# AFE.net
KiCad netlist of a schematic drawn in EAGLE
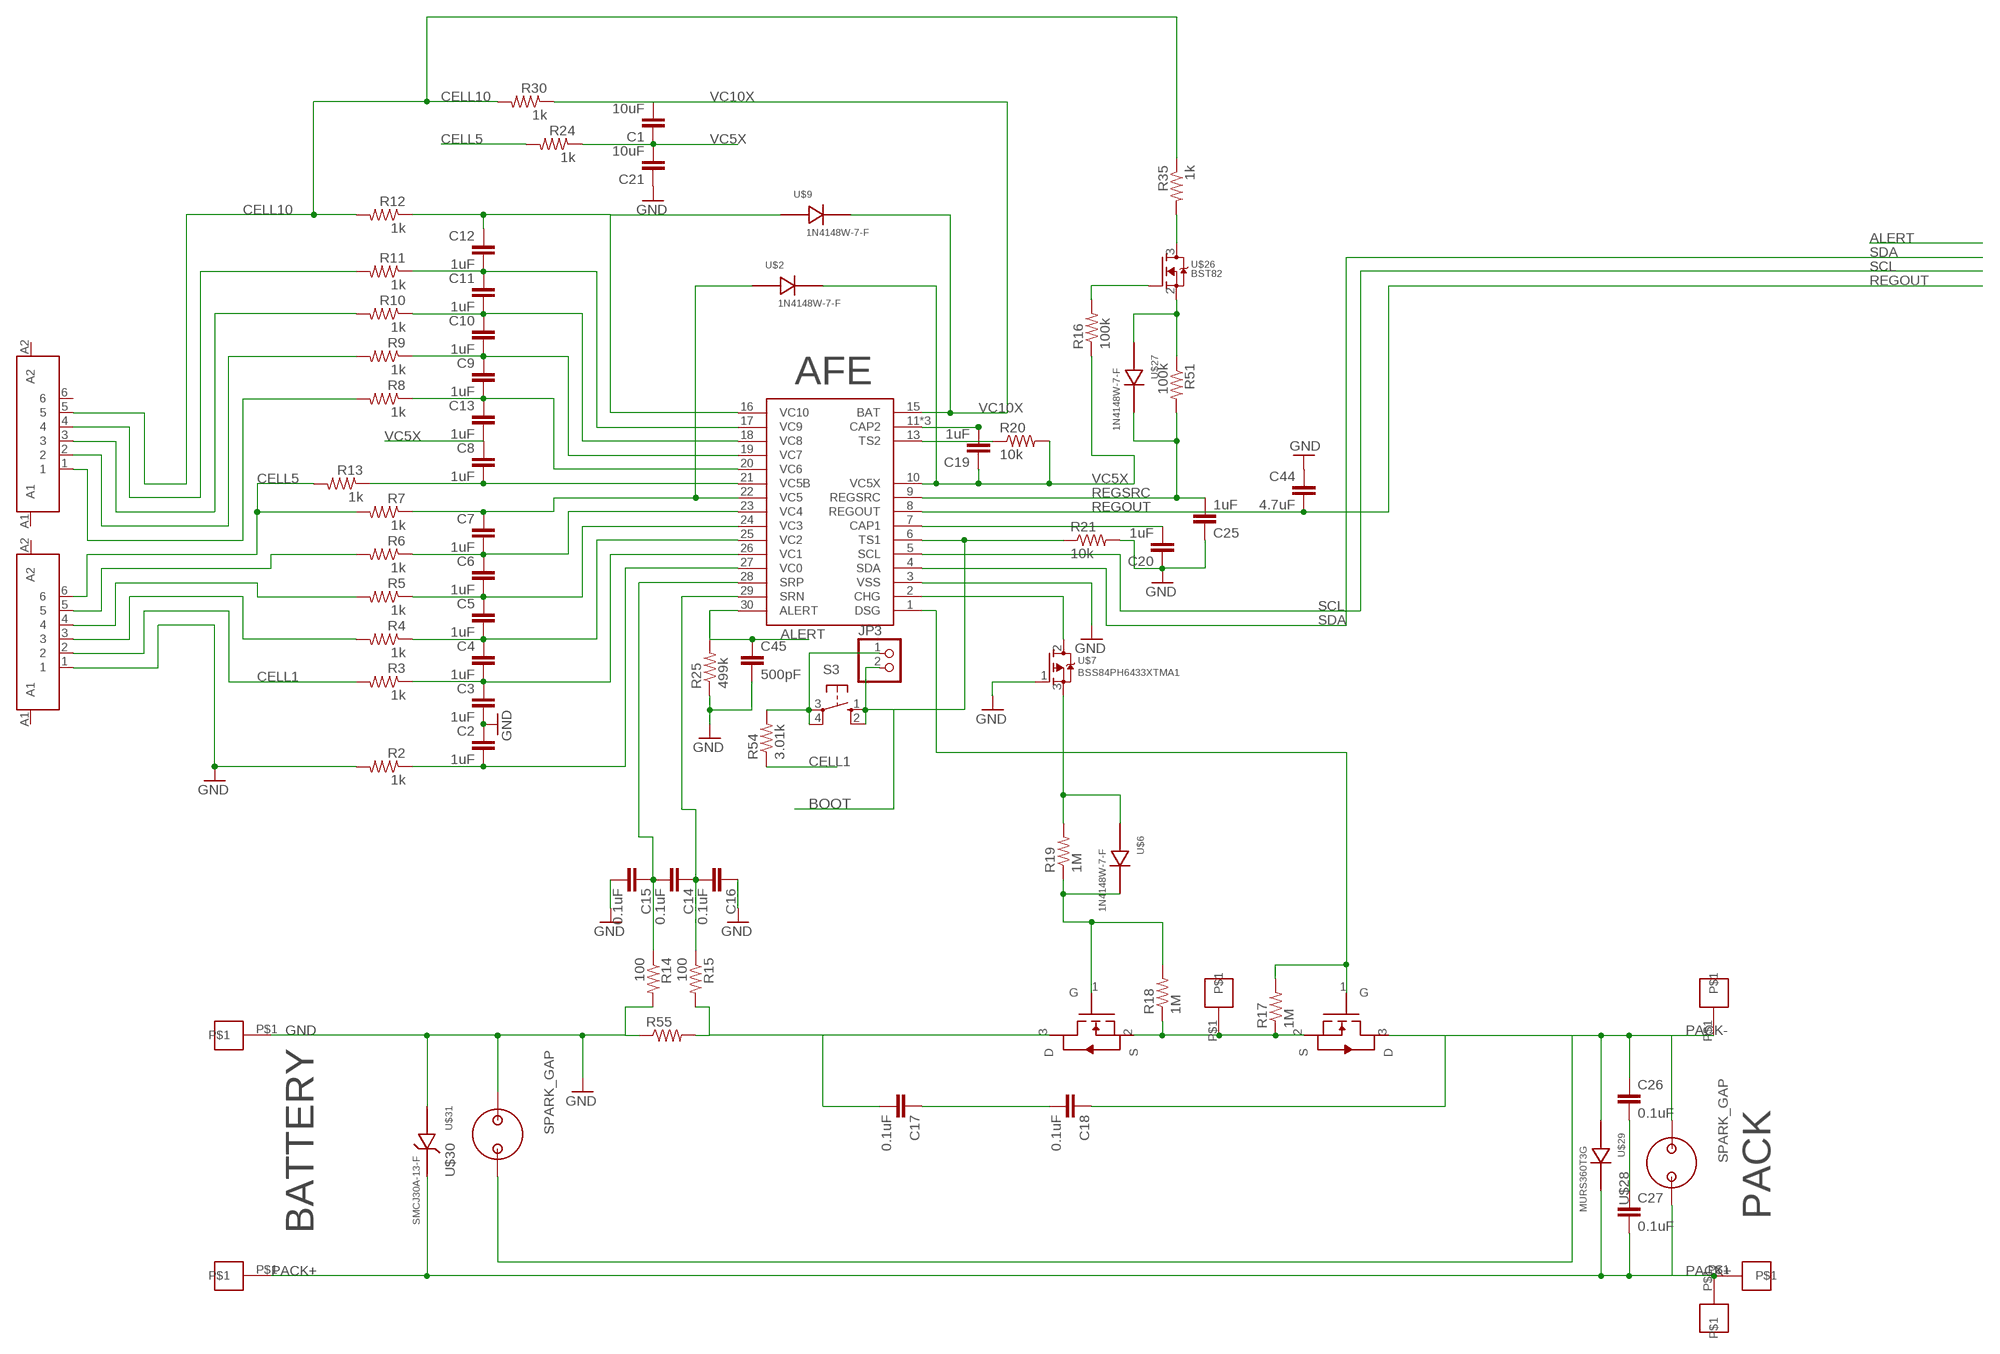
[diagram p0: schematic, sheet 1]
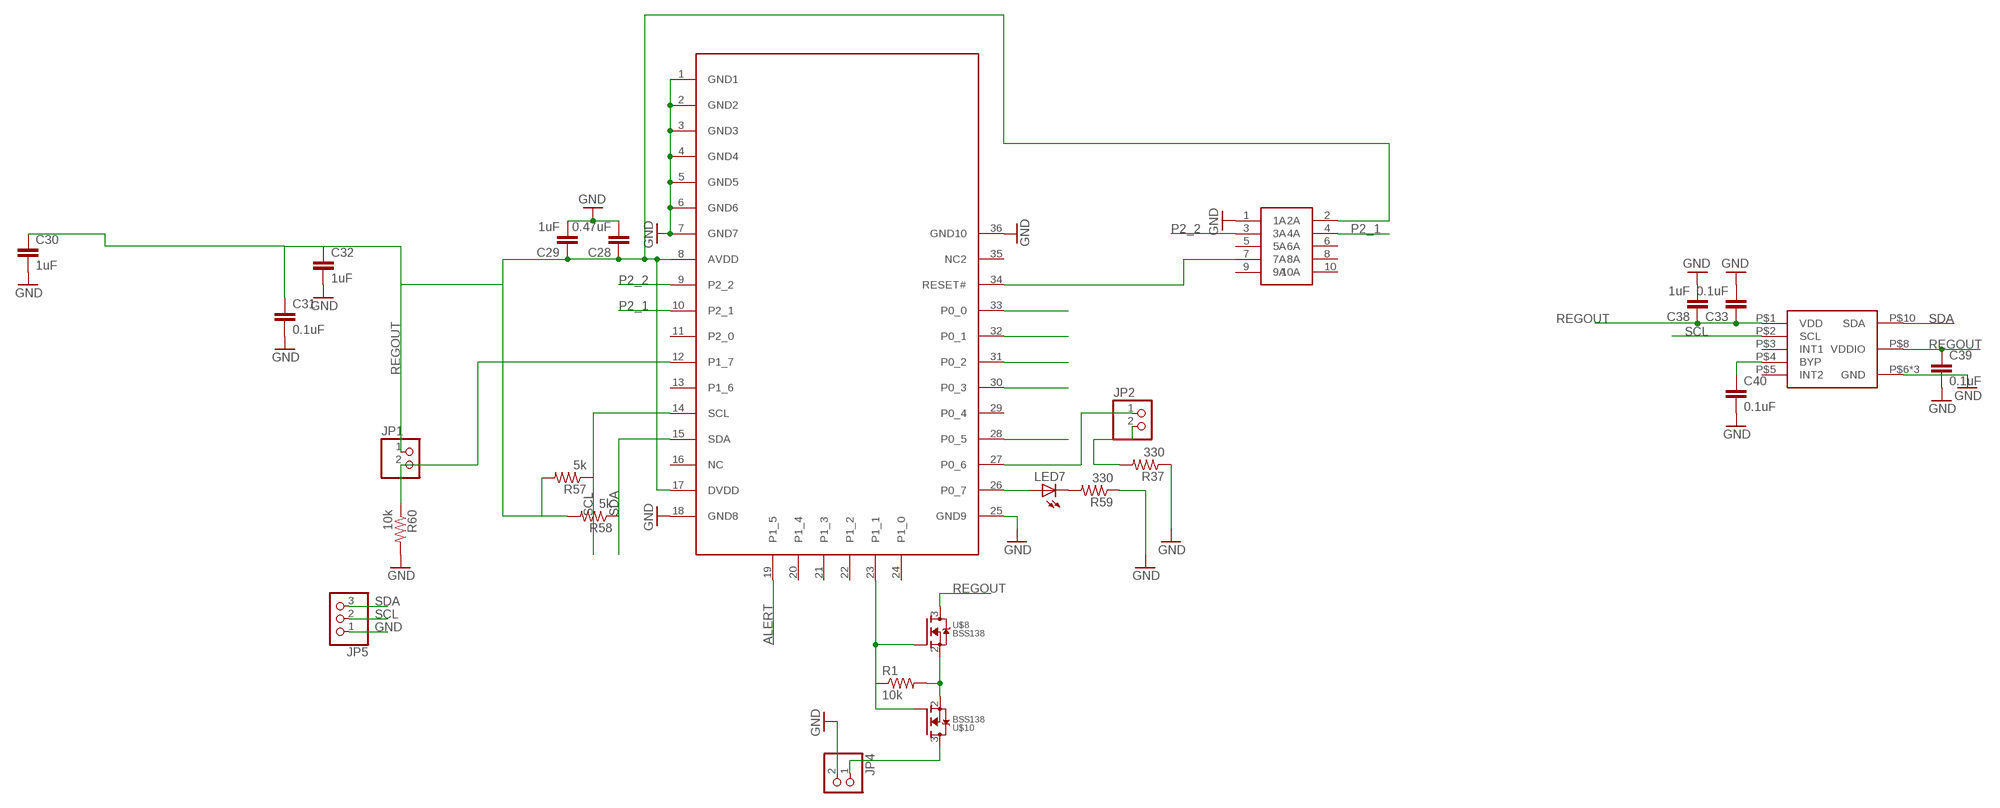
[diagram p1: schematic, sheet 2]

(export (version "E")
  (design (tool "Eeschema 10.0.6"))
  (components
    (comp (ref "C28")
      (value "0.47uF")
      (footprint "eagle-import:C0402")
      (libsource (lib "eagle-import") (part "C-EUC0402"))
    )
    (comp (ref "C29")
      (value "1uF")
      (footprint "eagle-import:C0402")
      (libsource (lib "eagle-import") (part "C-EUC0402"))
    )
    (comp (ref "C30")
      (value "1uF")
      (footprint "eagle-import:C0402")
      (libsource (lib "eagle-import") (part "C-EUC0402"))
    )
    (comp (ref "C31")
      (value "0.1uF")
      (footprint "eagle-import:C0402")
      (libsource (lib "eagle-import") (part "C-EUC0402"))
    )
    (comp (ref "C32")
      (value "1uF")
      (footprint "eagle-import:C0402")
      (libsource (lib "eagle-import") (part "C-EUC0402"))
    )
    (comp (ref "C33")
      (value "0.1uF")
      (footprint "eagle-import:C0402")
      (libsource (lib "eagle-import") (part "C-EUC0402"))
    )
    (comp (ref "C38")
      (value "1uF")
      (footprint "eagle-import:C0402")
      (libsource (lib "eagle-import") (part "C-EUC0402"))
    )
    (comp (ref "C39")
      (value "0.1uF")
      (footprint "eagle-import:C0402")
      (libsource (lib "eagle-import") (part "C-EUC0402"))
    )
    (comp (ref "C40")
      (value "0.1uF")
      (footprint "eagle-import:C0402")
      (libsource (lib "eagle-import") (part "C-EUC0402"))
    )
    (comp (ref "JP1")
      (value "PINHD-1X2")
      (footprint "eagle-import:1X02")
      (libsource (lib "eagle-import") (part "PINHD-1X2"))
    )
    (comp (ref "JP2")
      (value "PINHD-1X2")
      (footprint "eagle-import:1X02")
      (libsource (lib "eagle-import") (part "PINHD-1X2"))
    )
    (comp (ref "JP4")
      (value "PINHD-1X2")
      (footprint "eagle-import:1X02")
      (libsource (lib "eagle-import") (part "PINHD-1X2"))
    )
    (comp (ref "JP5")
      (value "PINHD-1X3")
      (footprint "eagle-import:1X03")
      (libsource (lib "eagle-import") (part "PINHD-1X3"))
    )
    (comp (ref "LED7")
      (value "LEDCHIP-LED0603")
      (footprint "eagle-import:CHIP-LED0603")
      (libsource (lib "eagle-import") (part "LEDCHIP-LED0603"))
    )
    (comp (ref "R1")
      (value "10k")
      (footprint "eagle-import:R0402")
      (libsource (lib "eagle-import") (part "R-US_R0402"))
    )
    (comp (ref "R37")
      (value "330")
      (footprint "eagle-import:R0402")
      (libsource (lib "eagle-import") (part "R-US_R0402"))
    )
    (comp (ref "R57")
      (value "5k")
      (footprint "eagle-import:R0402")
      (libsource (lib "eagle-import") (part "R-US_R0402"))
    )
    (comp (ref "R58")
      (value "5k")
      (footprint "eagle-import:R0402")
      (libsource (lib "eagle-import") (part "R-US_R0402"))
    )
    (comp (ref "R59")
      (value "330")
      (footprint "eagle-import:R0402")
      (libsource (lib "eagle-import") (part "R-US_R0402"))
    )
    (comp (ref "R60")
      (value "10k")
      (footprint "eagle-import:R0402")
      (libsource (lib "eagle-import") (part "R-US_R0402"))
    )
    (comp (ref "U$8")
      (value "BSS138")
      (footprint "eagle-import:SOT23-3")
      (libsource (lib "eagle-import") (part "BSS138"))
    )
    (comp (ref "U$10")
      (value "BSS138")
      (footprint "eagle-import:SOT23-3")
      (libsource (lib "eagle-import") (part "BSS138"))
    )
    (comp (ref "U$20")
      (value "BLE113")
      (footprint "eagle-import:BLUEGIGA")
      (libsource (lib "eagle-import") (part "BLE113"))
    )
    (comp (ref "U$22")
      (value "RIBBON_10POS_MALE")
      (footprint "eagle-import:RIBBON_10POS_MALE")
      (libsource (lib "eagle-import") (part "RIBBON_10POS_MALE"))
    )
    (comp (ref "U$32")
      (value "MMA8653FC")
      (footprint "eagle-import:10-DFN2X2")
      (libsource (lib "eagle-import") (part "MMA8653FC"))
    )
    (comp (ref "C1")
      (value "10uF")
      (footprint "eagle-import:C1210")
      (libsource (lib "eagle-import") (part "C-EUC1210"))
    )
    (comp (ref "C2")
      (value "1uF")
      (footprint "eagle-import:C0805")
      (libsource (lib "eagle-import") (part "C-EUC0805"))
    )
    (comp (ref "C3")
      (value "1uF")
      (footprint "eagle-import:C0805")
      (libsource (lib "eagle-import") (part "C-EUC0805"))
    )
    (comp (ref "C4")
      (value "1uF")
      (footprint "eagle-import:C0805")
      (libsource (lib "eagle-import") (part "C-EUC0805"))
    )
    (comp (ref "C5")
      (value "1uF")
      (footprint "eagle-import:C0805")
      (libsource (lib "eagle-import") (part "C-EUC0805"))
    )
    (comp (ref "C6")
      (value "1uF")
      (footprint "eagle-import:C0805")
      (libsource (lib "eagle-import") (part "C-EUC0805"))
    )
    (comp (ref "C7")
      (value "1uF")
      (footprint "eagle-import:C0805")
      (libsource (lib "eagle-import") (part "C-EUC0805"))
    )
    (comp (ref "C8")
      (value "1uF")
      (footprint "eagle-import:C0805")
      (libsource (lib "eagle-import") (part "C-EUC0805"))
    )
    (comp (ref "C9")
      (value "1uF")
      (footprint "eagle-import:C0805")
      (libsource (lib "eagle-import") (part "C-EUC0805"))
    )
    (comp (ref "C10")
      (value "1uF")
      (footprint "eagle-import:C0805")
      (libsource (lib "eagle-import") (part "C-EUC0805"))
    )
    (comp (ref "C11")
      (value "1uF")
      (footprint "eagle-import:C0805")
      (libsource (lib "eagle-import") (part "C-EUC0805"))
    )
    (comp (ref "C12")
      (value "1uF")
      (footprint "eagle-import:C0805")
      (libsource (lib "eagle-import") (part "C-EUC0805"))
    )
    (comp (ref "C13")
      (value "1uF")
      (footprint "eagle-import:C0805")
      (libsource (lib "eagle-import") (part "C-EUC0805"))
    )
    (comp (ref "C14")
      (value "0.1uF")
      (footprint "eagle-import:C0805")
      (libsource (lib "eagle-import") (part "C-EUC0805"))
    )
    (comp (ref "C15")
      (value "0.1uF")
      (footprint "eagle-import:C0805")
      (libsource (lib "eagle-import") (part "C-EUC0805"))
    )
    (comp (ref "C16")
      (value "0.1uF")
      (footprint "eagle-import:C0805")
      (libsource (lib "eagle-import") (part "C-EUC0805"))
    )
    (comp (ref "C17")
      (value "0.1uF")
      (footprint "eagle-import:C0805")
      (libsource (lib "eagle-import") (part "C-EUC0805"))
    )
    (comp (ref "C18")
      (value "0.1uF")
      (footprint "eagle-import:C0805")
      (libsource (lib "eagle-import") (part "C-EUC0805"))
    )
    (comp (ref "C19")
      (value "1uF")
      (footprint "eagle-import:C0805")
      (libsource (lib "eagle-import") (part "C-EUC0805"))
    )
    (comp (ref "C20")
      (value "1uF")
      (footprint "eagle-import:C0805")
      (libsource (lib "eagle-import") (part "C-EUC0805"))
    )
    (comp (ref "C21")
      (value "10uF")
      (footprint "eagle-import:C1210")
      (libsource (lib "eagle-import") (part "C-EUC1210"))
    )
    (comp (ref "C25")
      (value "1uF")
      (footprint "eagle-import:C0805")
      (libsource (lib "eagle-import") (part "C-EUC0805"))
    )
    (comp (ref "C26")
      (value "0.1uF")
      (footprint "eagle-import:C0805")
      (libsource (lib "eagle-import") (part "C-EUC0805"))
    )
    (comp (ref "C27")
      (value "0.1uF")
      (footprint "eagle-import:C0805")
      (libsource (lib "eagle-import") (part "C-EUC0805"))
    )
    (comp (ref "C44")
      (value "4.7uF")
      (footprint "eagle-import:C0805")
      (libsource (lib "eagle-import") (part "C-EUC0805"))
    )
    (comp (ref "C45")
      (value "500pF")
      (footprint "eagle-import:C0603")
      (libsource (lib "eagle-import") (part "C-EUC0603"))
    )
    (comp (ref "JP3")
      (value "PINHD-1X2")
      (footprint "eagle-import:1X02")
      (libsource (lib "eagle-import") (part "PINHD-1X2"))
    )
    (comp (ref "R2")
      (value "1k")
      (footprint "eagle-import:R1206")
      (libsource (lib "eagle-import") (part "R-US_R1206"))
    )
    (comp (ref "R3")
      (value "1k")
      (footprint "eagle-import:R1206")
      (libsource (lib "eagle-import") (part "R-US_R1206"))
    )
    (comp (ref "R4")
      (value "1k")
      (footprint "eagle-import:R1206")
      (libsource (lib "eagle-import") (part "R-US_R1206"))
    )
    (comp (ref "R5")
      (value "1k")
      (footprint "eagle-import:R1206")
      (libsource (lib "eagle-import") (part "R-US_R1206"))
    )
    (comp (ref "R6")
      (value "1k")
      (footprint "eagle-import:R1206")
      (libsource (lib "eagle-import") (part "R-US_R1206"))
    )
    (comp (ref "R7")
      (value "1k")
      (footprint "eagle-import:R1206")
      (libsource (lib "eagle-import") (part "R-US_R1206"))
    )
    (comp (ref "R8")
      (value "1k")
      (footprint "eagle-import:R1206")
      (libsource (lib "eagle-import") (part "R-US_R1206"))
    )
    (comp (ref "R9")
      (value "1k")
      (footprint "eagle-import:R1206")
      (libsource (lib "eagle-import") (part "R-US_R1206"))
    )
    (comp (ref "R10")
      (value "1k")
      (footprint "eagle-import:R1206")
      (libsource (lib "eagle-import") (part "R-US_R1206"))
    )
    (comp (ref "R11")
      (value "1k")
      (footprint "eagle-import:R1206")
      (libsource (lib "eagle-import") (part "R-US_R1206"))
    )
    (comp (ref "R12")
      (value "1k")
      (footprint "eagle-import:R1206")
      (libsource (lib "eagle-import") (part "R-US_R1206"))
    )
    (comp (ref "R13")
      (value "1k")
      (footprint "eagle-import:R1206")
      (libsource (lib "eagle-import") (part "R-US_R1206"))
    )
    (comp (ref "R14")
      (value "100")
      (footprint "eagle-import:R0805")
      (libsource (lib "eagle-import") (part "R-US_R0805"))
    )
    (comp (ref "R15")
      (value "100")
      (footprint "eagle-import:R0805")
      (libsource (lib "eagle-import") (part "R-US_R0805"))
    )
    (comp (ref "R16")
      (value "100k")
      (footprint "eagle-import:R0805")
      (libsource (lib "eagle-import") (part "R-US_R0805"))
    )
    (comp (ref "R17")
      (value "1M")
      (footprint "eagle-import:R1206")
      (libsource (lib "eagle-import") (part "R-US_R1206"))
    )
    (comp (ref "R18")
      (value "1M")
      (footprint "eagle-import:R1206")
      (libsource (lib "eagle-import") (part "R-US_R1206"))
    )
    (comp (ref "R19")
      (value "1M")
      (footprint "eagle-import:R1206")
      (libsource (lib "eagle-import") (part "R-US_R1206"))
    )
    (comp (ref "R20")
      (value "10k")
      (footprint "eagle-import:R0805")
      (libsource (lib "eagle-import") (part "R-US_R0805"))
    )
    (comp (ref "R21")
      (value "10k")
      (footprint "eagle-import:R0805")
      (libsource (lib "eagle-import") (part "R-US_R0805"))
    )
    (comp (ref "R24")
      (value "1k")
      (footprint "eagle-import:R1206")
      (libsource (lib "eagle-import") (part "R-US_R1206"))
    )
    (comp (ref "R25")
      (value "499k")
      (footprint "eagle-import:R0603")
      (libsource (lib "eagle-import") (part "R-US_R0603"))
    )
    (comp (ref "R30")
      (value "1k")
      (footprint "eagle-import:R1206")
      (libsource (lib "eagle-import") (part "R-US_R1206"))
    )
    (comp (ref "R35")
      (value "1k")
      (footprint "eagle-import:R1206")
      (libsource (lib "eagle-import") (part "R-US_R1206"))
    )
    (comp (ref "R51")
      (value "100k")
      (footprint "eagle-import:R0805")
      (libsource (lib "eagle-import") (part "R-US_R0805"))
    )
    (comp (ref "R54")
      (value "3.01k")
      (footprint "eagle-import:R1206")
      (libsource (lib "eagle-import") (part "R-US_R1206"))
    )
    (comp (ref "R55")
      (value "R-US_R2512")
      (footprint "eagle-import:R2512")
      (libsource (lib "eagle-import") (part "R-US_R2512"))
    )
    (comp (ref "S3")
      (value "10-XX")
      (footprint "eagle-import:B3F-10XX")
      (fields (field (name "MPN") "B3F-1000"))
      (libsource (lib "eagle-import") (part "10-XX"))
    )
    (comp (ref "U$1")
      (value "BQ76930")
      (footprint "eagle-import:SOIC-30")
      (libsource (lib "eagle-import") (part "BQ76930"))
    )
    (comp (ref "U$2")
      (value "1N4148W-7-F")
      (footprint "eagle-import:SOD-123")
      (libsource (lib "eagle-import") (part "1N4148W-7-F"))
    )
    (comp (ref "U$3")
      (value "PAD")
      (footprint "eagle-import:PAD")
      (libsource (lib "eagle-import") (part "PAD"))
    )
    (comp (ref "U$4")
      (value "AOB290L")
      (footprint "eagle-import:TO-263")
      (libsource (lib "eagle-import") (part "AOB290L"))
    )
    (comp (ref "U$5")
      (value "AOB290L")
      (footprint "eagle-import:TO-263")
      (libsource (lib "eagle-import") (part "AOB290L"))
    )
    (comp (ref "U$6")
      (value "1N4148W-7-F")
      (footprint "eagle-import:SOD-123")
      (libsource (lib "eagle-import") (part "1N4148W-7-F"))
    )
    (comp (ref "U$7")
      (value "BSS84PH6433XTMA1")
      (footprint "eagle-import:SOT23-3")
      (libsource (lib "eagle-import") (part "BSS84PH6433XTMA1"))
    )
    (comp (ref "U$9")
      (value "1N4148W-7-F")
      (footprint "eagle-import:SOD-123")
      (libsource (lib "eagle-import") (part "1N4148W-7-F"))
    )
    (comp (ref "U$24")
      (value "JST_6PIN")
      (footprint "eagle-import:JST_6PIN")
      (libsource (lib "eagle-import") (part "JST_6PIN"))
    )
    (comp (ref "U$26")
      (value "BST82")
      (footprint "eagle-import:SOT23-3")
      (libsource (lib "eagle-import") (part "BST82"))
    )
    (comp (ref "U$27")
      (value "1N4148W-7-F")
      (footprint "eagle-import:SOD-123")
      (libsource (lib "eagle-import") (part "1N4148W-7-F"))
    )
    (comp (ref "U$28")
      (value "SPARK_GAP")
      (footprint "eagle-import:SPARK_GAP")
      (libsource (lib "eagle-import") (part "SPARK_GAP"))
    )
    (comp (ref "U$29")
      (value "MURS360T3G")
      (footprint "eagle-import:SMC(DO-214AB)")
      (libsource (lib "eagle-import") (part "MURS360T3G"))
    )
    (comp (ref "U$30")
      (value "SPARK_GAP")
      (footprint "eagle-import:SPARK_GAP")
      (libsource (lib "eagle-import") (part "SPARK_GAP"))
    )
    (comp (ref "U$31")
      (value "SMCJ30A-13-F")
      (footprint "eagle-import:SMB(DO-214AA)")
      (libsource (lib "eagle-import") (part "SMCJ30A-13-F"))
    )
    (comp (ref "U$33")
      (value "JST_6PIN")
      (footprint "eagle-import:JST_6PIN")
      (libsource (lib "eagle-import") (part "JST_6PIN"))
    )
    (comp (ref "U$35")
      (value "PAD")
      (footprint "eagle-import:PAD")
      (libsource (lib "eagle-import") (part "PAD"))
    )
    (comp (ref "U$36")
      (value "PAD")
      (footprint "eagle-import:PAD")
      (libsource (lib "eagle-import") (part "PAD"))
    )
    (comp (ref "U$37")
      (value "PAD")
      (footprint "eagle-import:PAD")
      (libsource (lib "eagle-import") (part "PAD"))
    )
    (comp (ref "U$38")
      (value "PAD")
      (footprint "eagle-import:PAD")
      (libsource (lib "eagle-import") (part "PAD"))
    )
    (comp (ref "U$39")
      (value "PAD")
      (footprint "eagle-import:PAD")
      (libsource (lib "eagle-import") (part "PAD"))
    )
  )
  (nets
    (net (code "1") (name "ALERT") (class "Default")
      (node (ref "C45") (pin "1") (pinfunction "1_1") (pintype "passive"))
      (node (ref "R25") (pin "2") (pinfunction "2_2") (pintype "passive"))
      (node (ref "U$1") (pin "30") (pinfunction "ALERT_30") (pintype "bidirectional"))
      (node (ref "U$20") (pin "19") (pinfunction "P1_5_19") (pintype "bidirectional"))
    )
    (net (code "2") (name "BOOT") (class "Default")
      (node (ref "JP3") (pin "2") (pinfunction "2_2") (pintype "passive"))
      (node (ref "R21") (pin "1") (pinfunction "1_1") (pintype "passive"))
      (node (ref "S3") (pin "1") (pinfunction "S_1") (pintype "passive"))
      (node (ref "S3") (pin "2") (pinfunction "S1_2") (pintype "passive"))
      (node (ref "U$1") (pin "6") (pinfunction "TS1_6") (pintype "bidirectional"))
    )
    (net (code "3") (name "CELL1") (class "Default")
      (node (ref "R3") (pin "2") (pinfunction "2_2") (pintype "passive"))
      (node (ref "R54") (pin "1") (pinfunction "1_1") (pintype "passive"))
      (node (ref "U$33") (pin "2") (pinfunction "2_2") (pintype "bidirectional"))
    )
    (net (code "4") (name "CELL5") (class "Default")
      (node (ref "R13") (pin "2") (pinfunction "2_2") (pintype "passive"))
      (node (ref "R24") (pin "2") (pinfunction "2_2") (pintype "passive"))
      (node (ref "R7") (pin "2") (pinfunction "2_2") (pintype "passive"))
      (node (ref "U$33") (pin "6") (pinfunction "6_6") (pintype "bidirectional"))
    )
    (net (code "5") (name "CELL10") (class "Default")
      (node (ref "R12") (pin "2") (pinfunction "2_2") (pintype "passive"))
      (node (ref "R30") (pin "2") (pinfunction "2_2") (pintype "passive"))
      (node (ref "R35") (pin "1") (pinfunction "1_1") (pintype "passive"))
      (node (ref "U$24") (pin "5") (pinfunction "5_5") (pintype "bidirectional"))
    )
    (net (code "6") (name "GND") (class "Default")
      (node (ref "C15") (pin "2") (pinfunction "2_2") (pintype "passive"))
      (node (ref "C16") (pin "1") (pinfunction "1_1") (pintype "passive"))
      (node (ref "C2") (pin "1") (pinfunction "1_1") (pintype "passive"))
      (node (ref "C20") (pin "1") (pinfunction "1_1") (pintype "passive"))
      (node (ref "C21") (pin "1") (pinfunction "1_1") (pintype "passive"))
      (node (ref "C25") (pin "1") (pinfunction "1_1") (pintype "passive"))
      (node (ref "C28") (pin "2") (pinfunction "2_2") (pintype "passive"))
      (node (ref "C29") (pin "2") (pinfunction "2_2") (pintype "passive"))
      (node (ref "C3") (pin "2") (pinfunction "2_2") (pintype "passive"))
      (node (ref "C30") (pin "2") (pinfunction "2_2") (pintype "passive"))
      (node (ref "C31") (pin "2") (pinfunction "2_2") (pintype "passive"))
      (node (ref "C32") (pin "2") (pinfunction "2_2") (pintype "passive"))
      (node (ref "C33") (pin "2") (pinfunction "2_2") (pintype "passive"))
      (node (ref "C38") (pin "2") (pinfunction "2_2") (pintype "passive"))
      (node (ref "C39") (pin "2") (pinfunction "2_2") (pintype "passive"))
      (node (ref "C40") (pin "2") (pinfunction "2_2") (pintype "passive"))
      (node (ref "C44") (pin "1") (pinfunction "1_1") (pintype "passive"))
      (node (ref "C45") (pin "2") (pinfunction "2_2") (pintype "passive"))
      (node (ref "JP4") (pin "2") (pinfunction "2_2") (pintype "passive"))
      (node (ref "JP5") (pin "1") (pinfunction "1_1") (pintype "passive"))
      (node (ref "R14") (pin "2") (pinfunction "2_2") (pintype "passive"))
      (node (ref "R2") (pin "2") (pinfunction "2_2") (pintype "passive"))
      (node (ref "R21") (pin "2") (pinfunction "2_2") (pintype "passive"))
      (node (ref "R25") (pin "1") (pinfunction "1_1") (pintype "passive"))
      (node (ref "R37") (pin "1") (pinfunction "1_1") (pintype "passive"))
      (node (ref "R55") (pin "1") (pinfunction "1_1") (pintype "passive"))
      (node (ref "R59") (pin "1") (pinfunction "1_1") (pintype "passive"))
      (node (ref "R60") (pin "2") (pinfunction "2_2") (pintype "passive"))
      (node (ref "U$1") (pin "3") (pinfunction "VSS_3") (pintype "bidirectional"))
      (node (ref "U$20") (pin "1") (pinfunction "GND1_1") (pintype "bidirectional"))
      (node (ref "U$20") (pin "18") (pinfunction "GND8_18") (pintype "bidirectional"))
      (node (ref "U$20") (pin "2") (pinfunction "GND2_2") (pintype "bidirectional"))
      (node (ref "U$20") (pin "25") (pinfunction "GND9_25") (pintype "bidirectional"))
      (node (ref "U$20") (pin "3") (pinfunction "GND3_3") (pintype "bidirectional"))
      (node (ref "U$20") (pin "36") (pinfunction "GND10_36") (pintype "bidirectional"))
      (node (ref "U$20") (pin "4") (pinfunction "GND4_4") (pintype "bidirectional"))
      (node (ref "U$20") (pin "5") (pinfunction "GND5_5") (pintype "bidirectional"))
      (node (ref "U$20") (pin "6") (pinfunction "GND6_6") (pintype "bidirectional"))
      (node (ref "U$20") (pin "7") (pinfunction "GND7_7") (pintype "bidirectional"))
      (node (ref "U$22") (pin "1") (pinfunction "1A_1") (pintype "bidirectional"))
      (node (ref "U$3") (pin "P$1") (pinfunction "P$1_P$1") (pintype "bidirectional"))
      (node (ref "U$30") (pin "P$2") (pinfunction "P$2_P$2") (pintype "bidirectional"))
      (node (ref "U$31") (pin "P$1") (pinfunction "1_P$1") (pintype "bidirectional"))
      (node (ref "U$32") (pin "P$6") (pinfunction "GND_P$6") (pintype "bidirectional"))
      (node (ref "U$32") (pin "P$7") (pinfunction "GND_P$7") (pintype "bidirectional"))
      (node (ref "U$32") (pin "P$9") (pinfunction "GND_P$9") (pintype "bidirectional"))
      (node (ref "U$33") (pin "1") (pinfunction "1_1") (pintype "bidirectional"))
      (node (ref "U$7") (pin "1") (pinfunction "G_1") (pintype "bidirectional"))
    )
    (net (code "7") (name "Net-(C17-Pad1)") (class "Default")
      (node (ref "C17") (pin "1") (pinfunction "1_1") (pintype "passive"))
      (node (ref "C18") (pin "2") (pinfunction "2_2") (pintype "passive"))
    )
    (net (code "8") (name "Net-(C19-Pad2)") (class "Default")
      (node (ref "C19") (pin "2") (pinfunction "2_2") (pintype "passive"))
      (node (ref "U$1") (pin "11") (pinfunction "CAP2_11") (pintype "bidirectional"))
      (node (ref "U$1") (pin "12") (pinfunction "CAP2_12") (pintype "bidirectional"))
      (node (ref "U$1") (pin "14") (pinfunction "CAP2_14") (pintype "bidirectional"))
    )
    (net (code "9") (name "Net-(C26-Pad2)") (class "Default")
      (node (ref "C26") (pin "2") (pinfunction "2_2") (pintype "passive"))
      (node (ref "C27") (pin "1") (pinfunction "1_1") (pintype "passive"))
    )
    (net (code "10") (name "Net-(JP2-Pad2)") (class "Default")
      (node (ref "JP2") (pin "2") (pinfunction "2_2") (pintype "passive"))
      (node (ref "R37") (pin "2") (pinfunction "2_2") (pintype "passive"))
    )
    (net (code "11") (name "Net-(LED7-PadC)") (class "Default")
      (node (ref "LED7") (pin "C") (pinfunction "C_C") (pintype "passive"))
      (node (ref "R59") (pin "2") (pinfunction "2_2") (pintype "passive"))
    )
    (net (code "12") (name "Net-(R4-Pad2)") (class "Default")
      (node (ref "R4") (pin "2") (pinfunction "2_2") (pintype "passive"))
      (node (ref "U$33") (pin "3") (pinfunction "3_3") (pintype "bidirectional"))
    )
    (net (code "13") (name "Net-(R5-Pad2)") (class "Default")
      (node (ref "R5") (pin "2") (pinfunction "2_2") (pintype "passive"))
      (node (ref "U$33") (pin "4") (pinfunction "4_4") (pintype "bidirectional"))
    )
    (net (code "14") (name "Net-(R6-Pad2)") (class "Default")
      (node (ref "R6") (pin "2") (pinfunction "2_2") (pintype "passive"))
      (node (ref "U$33") (pin "5") (pinfunction "5_5") (pintype "bidirectional"))
    )
    (net (code "15") (name "Net-(R8-Pad2)") (class "Default")
      (node (ref "R8") (pin "2") (pinfunction "2_2") (pintype "passive"))
      (node (ref "U$24") (pin "1") (pinfunction "1_1") (pintype "bidirectional"))
    )
    (net (code "16") (name "Net-(R9-Pad2)") (class "Default")
      (node (ref "R9") (pin "2") (pinfunction "2_2") (pintype "passive"))
      (node (ref "U$24") (pin "2") (pinfunction "2_2") (pintype "bidirectional"))
    )
    (net (code "17") (name "Net-(R10-Pad2)") (class "Default")
      (node (ref "R10") (pin "2") (pinfunction "2_2") (pintype "passive"))
      (node (ref "U$24") (pin "3") (pinfunction "3_3") (pintype "bidirectional"))
    )
    (net (code "18") (name "Net-(R11-Pad2)") (class "Default")
      (node (ref "R11") (pin "2") (pinfunction "2_2") (pintype "passive"))
      (node (ref "U$24") (pin "4") (pinfunction "4_4") (pintype "bidirectional"))
    )
    (net (code "19") (name "Net-(S3-P)") (class "Default")
      (node (ref "JP3") (pin "1") (pinfunction "1_1") (pintype "passive"))
      (node (ref "R54") (pin "2") (pinfunction "2_2") (pintype "passive"))
      (node (ref "S3") (pin "3") (pinfunction "P_3") (pintype "passive"))
      (node (ref "S3") (pin "4") (pinfunction "P1_4") (pintype "passive"))
    )
    (net (code "20") (name "Net-(U$1-CAP1)") (class "Default")
      (node (ref "C20") (pin "2") (pinfunction "2_2") (pintype "passive"))
      (node (ref "U$1") (pin "7") (pinfunction "CAP1_7") (pintype "bidirectional"))
    )
    (net (code "21") (name "Net-(U$1-CHG)") (class "Default")
      (node (ref "U$1") (pin "2") (pinfunction "CHG_2") (pintype "bidirectional"))
      (node (ref "U$7") (pin "2") (pinfunction "S_2") (pintype "bidirectional"))
    )
    (net (code "22") (name "Net-(U$1-DSG)") (class "Default")
      (node (ref "R17") (pin "2") (pinfunction "2_2") (pintype "passive"))
      (node (ref "U$1") (pin "1") (pinfunction "DSG_1") (pintype "bidirectional"))
      (node (ref "U$4") (pin "1") (pinfunction "G_1") (pintype "bidirectional"))
    )
    (net (code "23") (name "Net-(U$1-SRN)") (class "Default")
      (node (ref "C14") (pin "1") (pinfunction "1_1") (pintype "passive"))
      (node (ref "C16") (pin "2") (pinfunction "2_2") (pintype "passive"))
      (node (ref "R15") (pin "1") (pinfunction "1_1") (pintype "passive"))
      (node (ref "U$1") (pin "29") (pinfunction "SRN_29") (pintype "bidirectional"))
    )
    (net (code "24") (name "Net-(U$1-SRP)") (class "Default")
      (node (ref "C14") (pin "2") (pinfunction "2_2") (pintype "passive"))
      (node (ref "C15") (pin "1") (pinfunction "1_1") (pintype "passive"))
      (node (ref "R14") (pin "1") (pinfunction "1_1") (pintype "passive"))
      (node (ref "U$1") (pin "28") (pinfunction "SRP_28") (pintype "bidirectional"))
    )
    (net (code "25") (name "Net-(U$1-TS2)") (class "Default")
      (node (ref "R20") (pin "1") (pinfunction "1_1") (pintype "passive"))
      (node (ref "U$1") (pin "13") (pinfunction "TS2_13") (pintype "bidirectional"))
    )
    (net (code "26") (name "Net-(U$1-VC0)") (class "Default")
      (node (ref "C2") (pin "2") (pinfunction "2_2") (pintype "passive"))
      (node (ref "R2") (pin "1") (pinfunction "1_1") (pintype "passive"))
      (node (ref "U$1") (pin "27") (pinfunction "VC0_27") (pintype "bidirectional"))
    )
    (net (code "27") (name "Net-(U$1-VC1)") (class "Default")
      (node (ref "C3") (pin "1") (pinfunction "1_1") (pintype "passive"))
      (node (ref "C4") (pin "2") (pinfunction "2_2") (pintype "passive"))
      (node (ref "R3") (pin "1") (pinfunction "1_1") (pintype "passive"))
      (node (ref "U$1") (pin "26") (pinfunction "VC1_26") (pintype "bidirectional"))
    )
    (net (code "28") (name "Net-(U$1-VC2)") (class "Default")
      (node (ref "C4") (pin "1") (pinfunction "1_1") (pintype "passive"))
      (node (ref "C5") (pin "2") (pinfunction "2_2") (pintype "passive"))
      (node (ref "R4") (pin "1") (pinfunction "1_1") (pintype "passive"))
      (node (ref "U$1") (pin "25") (pinfunction "VC2_25") (pintype "bidirectional"))
    )
    (net (code "29") (name "Net-(U$1-VC3)") (class "Default")
      (node (ref "C5") (pin "1") (pinfunction "1_1") (pintype "passive"))
      (node (ref "C6") (pin "2") (pinfunction "2_2") (pintype "passive"))
      (node (ref "R5") (pin "1") (pinfunction "1_1") (pintype "passive"))
      (node (ref "U$1") (pin "24") (pinfunction "VC3_24") (pintype "bidirectional"))
    )
    (net (code "30") (name "Net-(U$1-VC4)") (class "Default")
      (node (ref "C6") (pin "1") (pinfunction "1_1") (pintype "passive"))
      (node (ref "C7") (pin "2") (pinfunction "2_2") (pintype "passive"))
      (node (ref "R6") (pin "1") (pinfunction "1_1") (pintype "passive"))
      (node (ref "U$1") (pin "23") (pinfunction "VC4_23") (pintype "bidirectional"))
    )
    (net (code "31") (name "Net-(U$1-VC5)") (class "Default")
      (node (ref "C7") (pin "1") (pinfunction "1_1") (pintype "passive"))
      (node (ref "R7") (pin "1") (pinfunction "1_1") (pintype "passive"))
      (node (ref "U$1") (pin "22") (pinfunction "VC5_22") (pintype "bidirectional"))
      (node (ref "U$2") (pin "P$1") (pinfunction "P$1_P$1") (pintype "bidirectional"))
    )
    (net (code "32") (name "Net-(U$1-VC5B)") (class "Default")
      (node (ref "C8") (pin "2") (pinfunction "2_2") (pintype "passive"))
      (node (ref "R13") (pin "1") (pinfunction "1_1") (pintype "passive"))
      (node (ref "U$1") (pin "21") (pinfunction "VC5B_21") (pintype "bidirectional"))
    )
    (net (code "33") (name "Net-(U$1-VC6)") (class "Default")
      (node (ref "C13") (pin "1") (pinfunction "1_1") (pintype "passive"))
      (node (ref "C9") (pin "2") (pinfunction "2_2") (pintype "passive"))
      (node (ref "R8") (pin "1") (pinfunction "1_1") (pintype "passive"))
      (node (ref "U$1") (pin "20") (pinfunction "VC6_20") (pintype "bidirectional"))
    )
    (net (code "34") (name "Net-(U$1-VC7)") (class "Default")
      (node (ref "C10") (pin "2") (pinfunction "2_2") (pintype "passive"))
      (node (ref "C9") (pin "1") (pinfunction "1_1") (pintype "passive"))
      (node (ref "R9") (pin "1") (pinfunction "1_1") (pintype "passive"))
      (node (ref "U$1") (pin "19") (pinfunction "VC7_19") (pintype "bidirectional"))
    )
    (net (code "35") (name "Net-(U$1-VC8)") (class "Default")
      (node (ref "C10") (pin "1") (pinfunction "1_1") (pintype "passive"))
      (node (ref "C11") (pin "2") (pinfunction "2_2") (pintype "passive"))
      (node (ref "R10") (pin "1") (pinfunction "1_1") (pintype "passive"))
      (node (ref "U$1") (pin "18") (pinfunction "VC8_18") (pintype "bidirectional"))
    )
    (net (code "36") (name "Net-(U$1-VC9)") (class "Default")
      (node (ref "C11") (pin "1") (pinfunction "1_1") (pintype "passive"))
      (node (ref "C12") (pin "2") (pinfunction "2_2") (pintype "passive"))
      (node (ref "R11") (pin "1") (pinfunction "1_1") (pintype "passive"))
      (node (ref "U$1") (pin "17") (pinfunction "VC9_17") (pintype "bidirectional"))
    )
    (net (code "37") (name "Net-(U$1-VC10)") (class "Default")
      (node (ref "C12") (pin "1") (pinfunction "1_1") (pintype "passive"))
      (node (ref "R12") (pin "1") (pinfunction "1_1") (pintype "passive"))
      (node (ref "U$1") (pin "16") (pinfunction "VC10_16") (pintype "bidirectional"))
      (node (ref "U$9") (pin "P$1") (pinfunction "P$1_P$1") (pintype "bidirectional"))
    )
    (net (code "38") (name "Net-(U$4-S)") (class "Default")
      (node (ref "R17") (pin "1") (pinfunction "1_1") (pintype "passive"))
      (node (ref "R18") (pin "1") (pinfunction "1_1") (pintype "passive"))
      (node (ref "U$37") (pin "P$1") (pinfunction "P$1_P$1") (pintype "bidirectional"))
      (node (ref "U$4") (pin "2") (pinfunction "S_2") (pintype "bidirectional"))
      (node (ref "U$5") (pin "2") (pinfunction "S_2") (pintype "bidirectional"))
    )
    (net (code "39") (name "Net-(U$5-D)") (class "Default")
      (node (ref "C17") (pin "2") (pinfunction "2_2") (pintype "passive"))
      (node (ref "R15") (pin "2") (pinfunction "2_2") (pintype "passive"))
      (node (ref "R55") (pin "2") (pinfunction "2_2") (pintype "passive"))
      (node (ref "U$5") (pin "3") (pinfunction "D_3") (pintype "bidirectional"))
    )
    (net (code "40") (name "Net-(U$5-G)") (class "Default")
      (node (ref "R18") (pin "2") (pinfunction "2_2") (pintype "passive"))
      (node (ref "R19") (pin "1") (pinfunction "1_1") (pintype "passive"))
      (node (ref "U$5") (pin "1") (pinfunction "G_1") (pintype "bidirectional"))
      (node (ref "U$6") (pin "P$2") (pinfunction "P$2_P$2") (pintype "bidirectional"))
    )
    (net (code "41") (name "Net-(U$7-D)") (class "Default")
      (node (ref "R19") (pin "2") (pinfunction "2_2") (pintype "passive"))
      (node (ref "U$6") (pin "P$1") (pinfunction "P$1_P$1") (pintype "bidirectional"))
      (node (ref "U$7") (pin "3") (pinfunction "D_3") (pintype "bidirectional"))
    )
    (net (code "42") (name "Net-(U$10-D)") (class "Default")
      (node (ref "JP4") (pin "1") (pinfunction "1_1") (pintype "passive"))
      (node (ref "U$10") (pin "3") (pinfunction "D_3") (pintype "bidirectional"))
    )
    (net (code "43") (name "Net-(U$10-G)") (class "Default")
      (node (ref "R1") (pin "1") (pinfunction "1_1") (pintype "passive"))
      (node (ref "U$10") (pin "1") (pinfunction "G_1") (pintype "bidirectional"))
      (node (ref "U$20") (pin "23") (pinfunction "P1_1_23") (pintype "bidirectional"))
      (node (ref "U$8") (pin "1") (pinfunction "G_1") (pintype "bidirectional"))
    )
    (net (code "44") (name "Net-(U$10-S)") (class "Default")
      (node (ref "R1") (pin "2") (pinfunction "2_2") (pintype "passive"))
      (node (ref "U$10") (pin "2") (pinfunction "S_2") (pintype "bidirectional"))
      (node (ref "U$8") (pin "2") (pinfunction "S_2") (pintype "bidirectional"))
    )
    (net (code "45") (name "Net-(U$20-P0_6)") (class "Default")
      (node (ref "JP2") (pin "1") (pinfunction "1_1") (pintype "passive"))
      (node (ref "U$20") (pin "27") (pinfunction "P0_6_27") (pintype "bidirectional"))
    )
    (net (code "46") (name "Net-(U$20-P0_7)") (class "Default")
      (node (ref "LED7") (pin "A") (pinfunction "A_A") (pintype "passive"))
      (node (ref "U$20") (pin "26") (pinfunction "P0_7_26") (pintype "bidirectional"))
    )
    (net (code "47") (name "Net-(U$20-P1_7)") (class "Default")
      (node (ref "JP1") (pin "2") (pinfunction "2_2") (pintype "passive"))
      (node (ref "R60") (pin "1") (pinfunction "1_1") (pintype "passive"))
      (node (ref "U$20") (pin "12") (pinfunction "P1_7_12") (pintype "bidirectional"))
    )
    (net (code "48") (name "Net-(U$20-RESET#)") (class "Default")
      (node (ref "U$20") (pin "34") (pinfunction "RESET#_34") (pintype "bidirectional"))
      (node (ref "U$22") (pin "7") (pinfunction "7A_7") (pintype "bidirectional"))
    )
    (net (code "49") (name "Net-(U$26-D)") (class "Default")
      (node (ref "R35") (pin "2") (pinfunction "2_2") (pintype "passive"))
      (node (ref "U$26") (pin "3") (pinfunction "D_3") (pintype "bidirectional"))
    )
    (net (code "50") (name "Net-(U$26-G)") (class "Default")
      (node (ref "R16") (pin "2") (pinfunction "2_2") (pintype "passive"))
      (node (ref "U$26") (pin "1") (pinfunction "G_1") (pintype "bidirectional"))
    )
    (net (code "51") (name "Net-(U$26-S)") (class "Default")
      (node (ref "R51") (pin "1") (pinfunction "1_1") (pintype "passive"))
      (node (ref "U$26") (pin "2") (pinfunction "S_2") (pintype "bidirectional"))
      (node (ref "U$27") (pin "P$1") (pinfunction "P$1_P$1") (pintype "bidirectional"))
    )
    (net (code "52") (name "Net-(U$32-BYP)") (class "Default")
      (node (ref "C40") (pin "1") (pinfunction "1_1") (pintype "passive"))
      (node (ref "U$32") (pin "P$4") (pinfunction "BYP_P$4") (pintype "bidirectional"))
    )
    (net (code "53") (name "P2_1") (class "Default")
      (node (ref "U$20") (pin "10") (pinfunction "P2_1_10") (pintype "bidirectional"))
      (node (ref "U$22") (pin "4") (pinfunction "4A_4") (pintype "bidirectional"))
    )
    (net (code "54") (name "P2_2") (class "Default")
      (node (ref "U$20") (pin "9") (pinfunction "P2_2_9") (pintype "bidirectional"))
      (node (ref "U$22") (pin "3") (pinfunction "3A_3") (pintype "bidirectional"))
    )
    (net (code "55") (name "PACK+") (class "Default")
      (node (ref "C27") (pin "2") (pinfunction "2_2") (pintype "passive"))
      (node (ref "U$28") (pin "P$1") (pinfunction "P$1_P$1") (pintype "bidirectional"))
      (node (ref "U$29") (pin "2") (pinfunction "P$2_2") (pintype "bidirectional"))
      (node (ref "U$31") (pin "P$2") (pinfunction "2_P$2") (pintype "bidirectional"))
      (node (ref "U$35") (pin "P$1") (pinfunction "P$1_P$1") (pintype "bidirectional"))
      (node (ref "U$36") (pin "P$1") (pinfunction "P$1_P$1") (pintype "bidirectional"))
      (node (ref "U$39") (pin "P$1") (pinfunction "P$1_P$1") (pintype "bidirectional"))
    )
    (net (code "56") (name "PACK-") (class "Default")
      (node (ref "C18") (pin "1") (pinfunction "1_1") (pintype "passive"))
      (node (ref "C26") (pin "1") (pinfunction "1_1") (pintype "passive"))
      (node (ref "U$28") (pin "P$2") (pinfunction "P$2_P$2") (pintype "bidirectional"))
      (node (ref "U$29") (pin "1") (pinfunction "P$1_1") (pintype "bidirectional"))
      (node (ref "U$30") (pin "P$1") (pinfunction "P$1_P$1") (pintype "bidirectional"))
      (node (ref "U$38") (pin "P$1") (pinfunction "P$1_P$1") (pintype "bidirectional"))
      (node (ref "U$4") (pin "3") (pinfunction "D_3") (pintype "bidirectional"))
    )
    (net (code "57") (name "REGOUT") (class "Default")
      (node (ref "C28") (pin "1") (pinfunction "1_1") (pintype "passive"))
      (node (ref "C29") (pin "1") (pinfunction "1_1") (pintype "passive"))
      (node (ref "C30") (pin "1") (pinfunction "1_1") (pintype "passive"))
      (node (ref "C31") (pin "1") (pinfunction "1_1") (pintype "passive"))
      (node (ref "C32") (pin "1") (pinfunction "1_1") (pintype "passive"))
      (node (ref "C33") (pin "1") (pinfunction "1_1") (pintype "passive"))
      (node (ref "C38") (pin "1") (pinfunction "1_1") (pintype "passive"))
      (node (ref "C39") (pin "1") (pinfunction "1_1") (pintype "passive"))
      (node (ref "C44") (pin "2") (pinfunction "2_2") (pintype "passive"))
      (node (ref "JP1") (pin "1") (pinfunction "1_1") (pintype "passive"))
      (node (ref "R57") (pin "2") (pinfunction "2_2") (pintype "passive"))
      (node (ref "R58") (pin "2") (pinfunction "2_2") (pintype "passive"))
      (node (ref "U$1") (pin "8") (pinfunction "REGOUT_8") (pintype "bidirectional"))
      (node (ref "U$20") (pin "17") (pinfunction "DVDD_17") (pintype "bidirectional"))
      (node (ref "U$20") (pin "8") (pinfunction "AVDD_8") (pintype "bidirectional"))
      (node (ref "U$22") (pin "2") (pinfunction "2A_2") (pintype "bidirectional"))
      (node (ref "U$32") (pin "P$1") (pinfunction "VDD_P$1") (pintype "bidirectional"))
      (node (ref "U$32") (pin "P$8") (pinfunction "VDDIO_P$8") (pintype "bidirectional"))
      (node (ref "U$8") (pin "3") (pinfunction "D_3") (pintype "bidirectional"))
    )
    (net (code "58") (name "REGSRC") (class "Default")
      (node (ref "C25") (pin "2") (pinfunction "2_2") (pintype "passive"))
      (node (ref "R51") (pin "2") (pinfunction "2_2") (pintype "passive"))
      (node (ref "U$1") (pin "9") (pinfunction "REGSRC_9") (pintype "bidirectional"))
      (node (ref "U$27") (pin "P$2") (pinfunction "P$2_P$2") (pintype "bidirectional"))
    )
    (net (code "59") (name "SCL") (class "Default")
      (node (ref "JP5") (pin "2") (pinfunction "2_2") (pintype "passive"))
      (node (ref "R57") (pin "1") (pinfunction "1_1") (pintype "passive"))
      (node (ref "U$1") (pin "5") (pinfunction "SCL_5") (pintype "bidirectional"))
      (node (ref "U$20") (pin "14") (pinfunction "SCL_14") (pintype "bidirectional"))
      (node (ref "U$32") (pin "P$2") (pinfunction "SCL_P$2") (pintype "bidirectional"))
    )
    (net (code "60") (name "SDA") (class "Default")
      (node (ref "JP5") (pin "3") (pinfunction "3_3") (pintype "passive"))
      (node (ref "R58") (pin "1") (pinfunction "1_1") (pintype "passive"))
      (node (ref "U$1") (pin "4") (pinfunction "SDA_4") (pintype "bidirectional"))
      (node (ref "U$20") (pin "15") (pinfunction "SDA_15") (pintype "bidirectional"))
      (node (ref "U$32") (pin "P$10") (pinfunction "SDA_P$10") (pintype "bidirectional"))
    )
    (net (code "61") (name "VC5X") (class "Default")
      (node (ref "C1") (pin "1") (pinfunction "1_1") (pintype "passive"))
      (node (ref "C13") (pin "2") (pinfunction "2_2") (pintype "passive"))
      (node (ref "C19") (pin "1") (pinfunction "1_1") (pintype "passive"))
      (node (ref "C21") (pin "2") (pinfunction "2_2") (pintype "passive"))
      (node (ref "C8") (pin "1") (pinfunction "1_1") (pintype "passive"))
      (node (ref "R16") (pin "1") (pinfunction "1_1") (pintype "passive"))
      (node (ref "R20") (pin "2") (pinfunction "2_2") (pintype "passive"))
      (node (ref "R24") (pin "1") (pinfunction "1_1") (pintype "passive"))
      (node (ref "U$1") (pin "10") (pinfunction "VC5X_10") (pintype "bidirectional"))
      (node (ref "U$2") (pin "P$2") (pinfunction "P$2_P$2") (pintype "bidirectional"))
    )
    (net (code "62") (name "VC10X") (class "Default")
      (node (ref "C1") (pin "2") (pinfunction "2_2") (pintype "passive"))
      (node (ref "R30") (pin "1") (pinfunction "1_1") (pintype "passive"))
      (node (ref "U$1") (pin "15") (pinfunction "BAT_15") (pintype "bidirectional"))
      (node (ref "U$9") (pin "P$2") (pinfunction "P$2_P$2") (pintype "bidirectional"))
    )
    (net (code "63") (name "unconnected-(U$20-NC-Pad16)") (class "Default")
      (node (ref "U$20") (pin "16") (pinfunction "NC_16") (pintype "bidirectional"))
    )
    (net (code "64") (name "unconnected-(U$20-NC2-Pad35)") (class "Default")
      (node (ref "U$20") (pin "35") (pinfunction "NC2_35") (pintype "bidirectional"))
    )
    (net (code "65") (name "unconnected-(U$20-P0_0-Pad33)") (class "Default")
      (node (ref "U$20") (pin "33") (pinfunction "P0_0_33") (pintype "bidirectional"))
    )
    (net (code "66") (name "unconnected-(U$20-P0_1-Pad32)") (class "Default")
      (node (ref "U$20") (pin "32") (pinfunction "P0_1_32") (pintype "bidirectional"))
    )
    (net (code "67") (name "unconnected-(U$20-P0_2-Pad31)") (class "Default")
      (node (ref "U$20") (pin "31") (pinfunction "P0_2_31") (pintype "bidirectional"))
    )
    (net (code "68") (name "unconnected-(U$20-P0_3-Pad30)") (class "Default")
      (node (ref "U$20") (pin "30") (pinfunction "P0_3_30") (pintype "bidirectional"))
    )
    (net (code "69") (name "unconnected-(U$20-P0_4-Pad29)") (class "Default")
      (node (ref "U$20") (pin "29") (pinfunction "P0_4_29") (pintype "bidirectional"))
    )
    (net (code "70") (name "unconnected-(U$20-P0_5-Pad28)") (class "Default")
      (node (ref "U$20") (pin "28") (pinfunction "P0_5_28") (pintype "bidirectional"))
    )
    (net (code "71") (name "unconnected-(U$20-P1_0-Pad24)") (class "Default")
      (node (ref "U$20") (pin "24") (pinfunction "P1_0_24") (pintype "bidirectional"))
    )
    (net (code "72") (name "unconnected-(U$20-P1_2-Pad22)") (class "Default")
      (node (ref "U$20") (pin "22") (pinfunction "P1_2_22") (pintype "bidirectional"))
    )
    (net (code "73") (name "unconnected-(U$20-P1_3-Pad21)") (class "Default")
      (node (ref "U$20") (pin "21") (pinfunction "P1_3_21") (pintype "bidirectional"))
    )
    (net (code "74") (name "unconnected-(U$20-P1_4-Pad20)") (class "Default")
      (node (ref "U$20") (pin "20") (pinfunction "P1_4_20") (pintype "bidirectional"))
    )
    (net (code "75") (name "unconnected-(U$20-P1_6-Pad13)") (class "Default")
      (node (ref "U$20") (pin "13") (pinfunction "P1_6_13") (pintype "bidirectional"))
    )
    (net (code "76") (name "unconnected-(U$20-P2_0-Pad11)") (class "Default")
      (node (ref "U$20") (pin "11") (pinfunction "P2_0_11") (pintype "bidirectional"))
    )
    (net (code "77") (name "unconnected-(U$22-5A-Pad5)") (class "Default")
      (node (ref "U$22") (pin "5") (pinfunction "5A_5") (pintype "bidirectional"))
    )
    (net (code "78") (name "unconnected-(U$22-6A-Pad6)") (class "Default")
      (node (ref "U$22") (pin "6") (pinfunction "6A_6") (pintype "bidirectional"))
    )
    (net (code "79") (name "unconnected-(U$22-8A-Pad8)") (class "Default")
      (node (ref "U$22") (pin "8") (pinfunction "8A_8") (pintype "bidirectional"))
    )
    (net (code "80") (name "unconnected-(U$22-9A-Pad9)") (class "Default")
      (node (ref "U$22") (pin "9") (pinfunction "9A_9") (pintype "bidirectional"))
    )
    (net (code "81") (name "unconnected-(U$22-10A-Pad10)") (class "Default")
      (node (ref "U$22") (pin "10") (pinfunction "10A_10") (pintype "bidirectional"))
    )
    (net (code "82") (name "unconnected-(U$24-Pad6)") (class "Default")
      (node (ref "U$24") (pin "6") (pinfunction "6_6") (pintype "bidirectional"))
    )
    (net (code "83") (name "unconnected-(U$24-PadA1)") (class "Default")
      (node (ref "U$24") (pin "A1") (pinfunction "A1_A1") (pintype "bidirectional"))
    )
    (net (code "84") (name "unconnected-(U$24-PadA2)") (class "Default")
      (node (ref "U$24") (pin "A2") (pinfunction "A2_A2") (pintype "bidirectional"))
    )
    (net (code "85") (name "unconnected-(U$32-INT1-PadP$3)") (class "Default")
      (node (ref "U$32") (pin "P$3") (pinfunction "INT1_P$3") (pintype "bidirectional"))
    )
    (net (code "86") (name "unconnected-(U$32-INT2-PadP$5)") (class "Default")
      (node (ref "U$32") (pin "P$5") (pinfunction "INT2_P$5") (pintype "bidirectional"))
    )
    (net (code "87") (name "unconnected-(U$33-PadA1)") (class "Default")
      (node (ref "U$33") (pin "A1") (pinfunction "A1_A1") (pintype "bidirectional"))
    )
    (net (code "88") (name "unconnected-(U$33-PadA2)") (class "Default")
      (node (ref "U$33") (pin "A2") (pinfunction "A2_A2") (pintype "bidirectional"))
    )
  )
)
